# CAN.net
KiCad netlist of a schematic drawn in Altium Designer
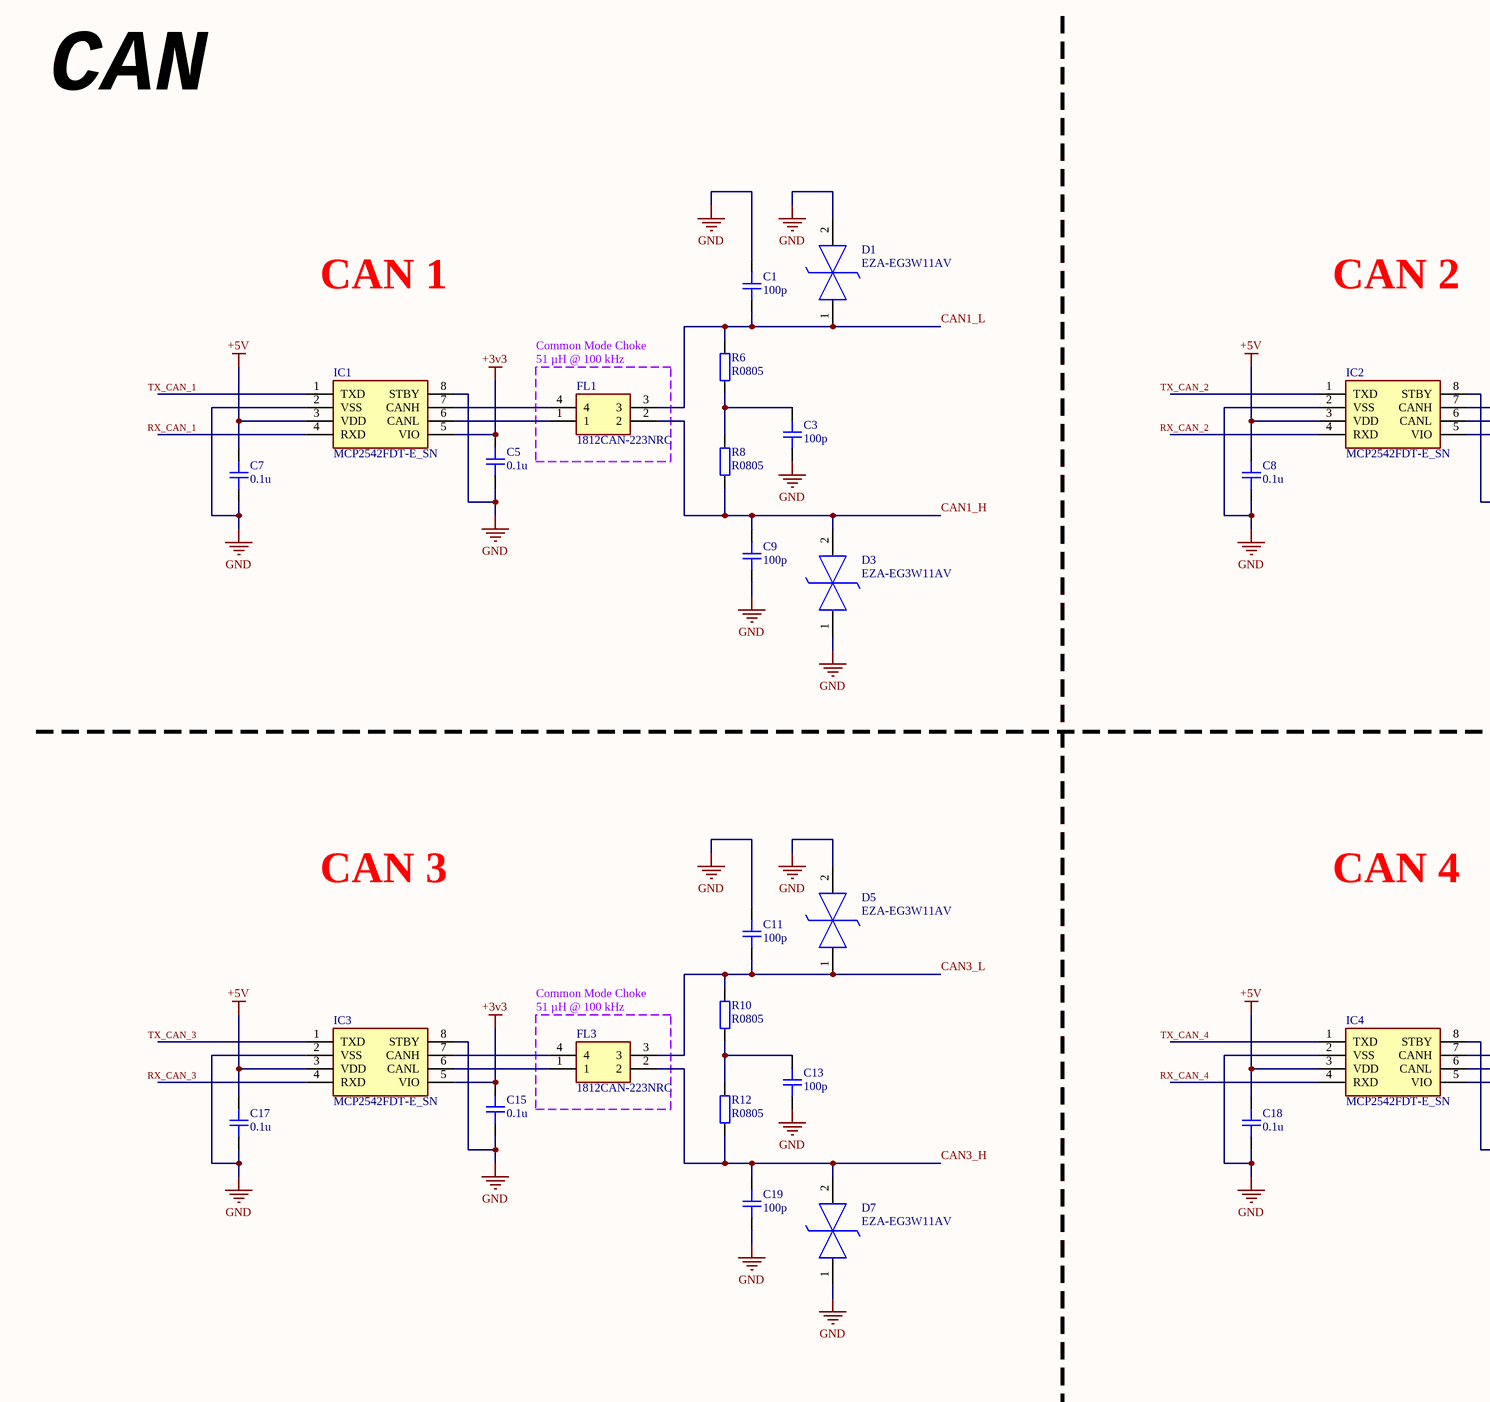
[diagram p0: CAN.SchDoc, left]
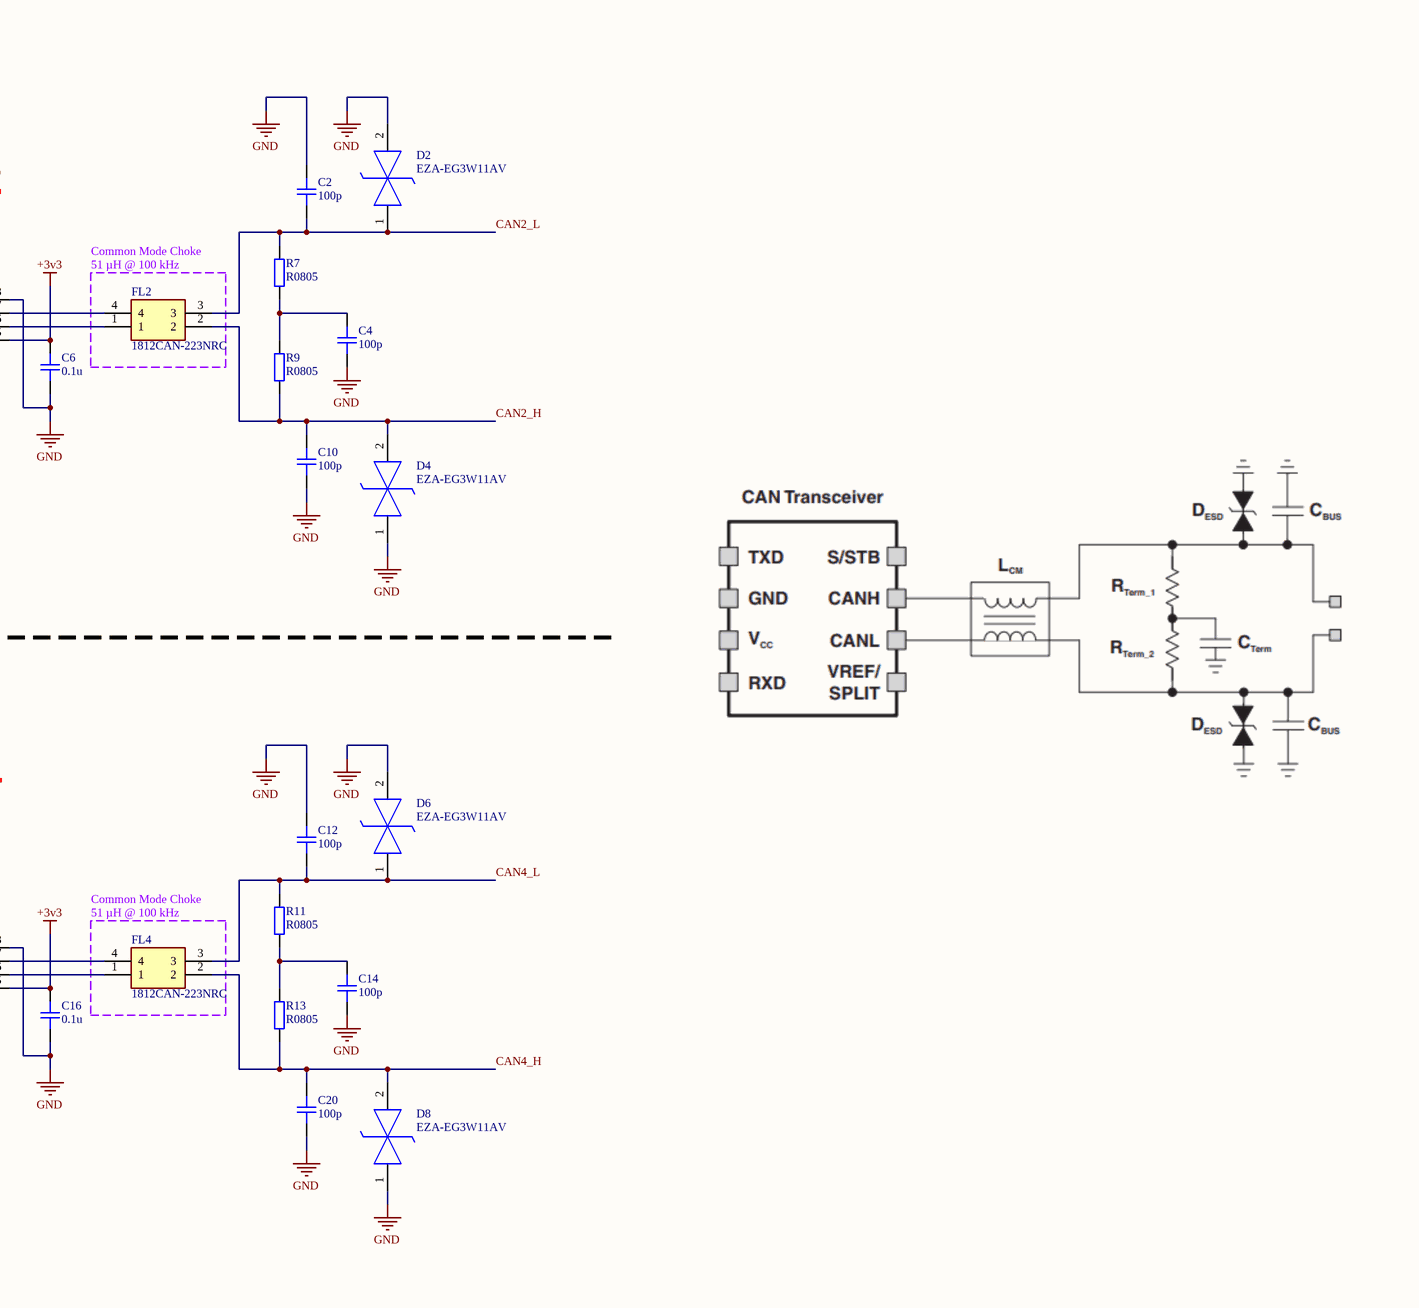
[diagram p1: CAN.SchDoc, right]

(export (version "E")
  (design (tool "Eeschema 10.0.6"))
  (components
    (comp (ref "C1")
      (value "100p")
      (footprint "CAP_0805")
      (description "Capacitor SMD 0805 10V")
      (libsource (lib "Schematic-Lib-PhilsLab") (part "CAP_0805_10V"))
    )
    (comp (ref "C2")
      (value "100p")
      (footprint "CAP_0805")
      (description "Capacitor SMD 0805 10V")
      (libsource (lib "Schematic-Lib-PhilsLab") (part "CAP_0805_10V"))
    )
    (comp (ref "C3")
      (value "100p")
      (footprint "CAP_0805")
      (description "Capacitor SMD 0805 10V")
      (libsource (lib "Schematic-Lib-PhilsLab") (part "CAP_0805_10V"))
    )
    (comp (ref "C4")
      (value "100p")
      (footprint "CAP_0805")
      (description "Capacitor SMD 0805 10V")
      (libsource (lib "Schematic-Lib-PhilsLab") (part "CAP_0805_10V"))
    )
    (comp (ref "C5")
      (value "0.1u")
      (footprint "CAP_0805")
      (description "Capacitor SMD 0805 10V")
      (libsource (lib "Schematic-Lib-PhilsLab") (part "CAP_0805_10V"))
    )
    (comp (ref "C6")
      (value "0.1u")
      (footprint "CAP_0805")
      (description "Capacitor SMD 0805 10V")
      (libsource (lib "Schematic-Lib-PhilsLab") (part "CAP_0805_10V"))
    )
    (comp (ref "C7")
      (value "0.1u")
      (footprint "CAP_0805")
      (description "Capacitor SMD 0805 10V")
      (libsource (lib "Schematic-Lib-PhilsLab") (part "CAP_0805_10V"))
    )
    (comp (ref "C8")
      (value "0.1u")
      (footprint "CAP_0805")
      (description "Capacitor SMD 0805 10V")
      (libsource (lib "Schematic-Lib-PhilsLab") (part "CAP_0805_10V"))
    )
    (comp (ref "C9")
      (value "100p")
      (footprint "CAP_0805")
      (description "Capacitor SMD 0805 10V")
      (libsource (lib "Schematic-Lib-PhilsLab") (part "CAP_0805_10V"))
    )
    (comp (ref "C10")
      (value "100p")
      (footprint "CAP_0805")
      (description "Capacitor SMD 0805 10V")
      (libsource (lib "Schematic-Lib-PhilsLab") (part "CAP_0805_10V"))
    )
    (comp (ref "C11")
      (value "100p")
      (footprint "CAP_0805")
      (description "Capacitor SMD 0805 10V")
      (libsource (lib "Schematic-Lib-PhilsLab") (part "CAP_0805_10V"))
    )
    (comp (ref "C12")
      (value "100p")
      (footprint "CAP_0805")
      (description "Capacitor SMD 0805 10V")
      (libsource (lib "Schematic-Lib-PhilsLab") (part "CAP_0805_10V"))
    )
    (comp (ref "C13")
      (value "100p")
      (footprint "CAP_0805")
      (description "Capacitor SMD 0805 10V")
      (libsource (lib "Schematic-Lib-PhilsLab") (part "CAP_0805_10V"))
    )
    (comp (ref "C14")
      (value "100p")
      (footprint "CAP_0805")
      (description "Capacitor SMD 0805 10V")
      (libsource (lib "Schematic-Lib-PhilsLab") (part "CAP_0805_10V"))
    )
    (comp (ref "C15")
      (value "0.1u")
      (footprint "CAP_0805")
      (description "Capacitor SMD 0805 10V")
      (libsource (lib "Schematic-Lib-PhilsLab") (part "CAP_0805_10V"))
    )
    (comp (ref "C16")
      (value "0.1u")
      (footprint "CAP_0805")
      (description "Capacitor SMD 0805 10V")
      (libsource (lib "Schematic-Lib-PhilsLab") (part "CAP_0805_10V"))
    )
    (comp (ref "C17")
      (value "0.1u")
      (footprint "CAP_0805")
      (description "Capacitor SMD 0805 10V")
      (libsource (lib "Schematic-Lib-PhilsLab") (part "CAP_0805_10V"))
    )
    (comp (ref "C18")
      (value "0.1u")
      (footprint "CAP_0805")
      (description "Capacitor SMD 0805 10V")
      (libsource (lib "Schematic-Lib-PhilsLab") (part "CAP_0805_10V"))
    )
    (comp (ref "C19")
      (value "100p")
      (footprint "CAP_0805")
      (description "Capacitor SMD 0805 10V")
      (libsource (lib "Schematic-Lib-PhilsLab") (part "CAP_0805_10V"))
    )
    (comp (ref "C20")
      (value "100p")
      (footprint "CAP_0805")
      (description "Capacitor SMD 0805 10V")
      (libsource (lib "Schematic-Lib-PhilsLab") (part "CAP_0805_10V"))
    )
    (comp (ref "D1")
      (value "EZA-EG3W11AV")
      (footprint "EZAEG3W11AV")
      (description "Diode ESD (Bi-directional)")
      (fields (field (name "MOUSER PART NUMBER") "667-EZA-EG3W11AV"))
      (libsource (lib "Pedro_Integrated_Library") (part "EZA-EG3W11AV"))
    )
    (comp (ref "D2")
      (value "EZA-EG3W11AV")
      (footprint "EZAEG3W11AV")
      (description "Diode ESD (Bi-directional)")
      (fields (field (name "MOUSER PART NUMBER") "667-EZA-EG3W11AV"))
      (libsource (lib "Pedro_Integrated_Library") (part "EZA-EG3W11AV"))
    )
    (comp (ref "D3")
      (value "EZA-EG3W11AV")
      (footprint "EZAEG3W11AV")
      (description "Diode ESD (Bi-directional)")
      (fields (field (name "MOUSER PART NUMBER") "667-EZA-EG3W11AV"))
      (libsource (lib "Pedro_Integrated_Library") (part "EZA-EG3W11AV"))
    )
    (comp (ref "D4")
      (value "EZA-EG3W11AV")
      (footprint "EZAEG3W11AV")
      (description "Diode ESD (Bi-directional)")
      (fields (field (name "MOUSER PART NUMBER") "667-EZA-EG3W11AV"))
      (libsource (lib "Pedro_Integrated_Library") (part "EZA-EG3W11AV"))
    )
    (comp (ref "D5")
      (value "EZA-EG3W11AV")
      (footprint "EZAEG3W11AV")
      (description "Diode ESD (Bi-directional)")
      (fields (field (name "MOUSER PART NUMBER") "667-EZA-EG3W11AV"))
      (libsource (lib "Pedro_Integrated_Library") (part "EZA-EG3W11AV"))
    )
    (comp (ref "D6")
      (value "EZA-EG3W11AV")
      (footprint "EZAEG3W11AV")
      (description "Diode ESD (Bi-directional)")
      (fields (field (name "MOUSER PART NUMBER") "667-EZA-EG3W11AV"))
      (libsource (lib "Pedro_Integrated_Library") (part "EZA-EG3W11AV"))
    )
    (comp (ref "D7")
      (value "EZA-EG3W11AV")
      (footprint "EZAEG3W11AV")
      (description "Diode ESD (Bi-directional)")
      (fields (field (name "MOUSER PART NUMBER") "667-EZA-EG3W11AV"))
      (libsource (lib "Pedro_Integrated_Library") (part "EZA-EG3W11AV"))
    )
    (comp (ref "D8")
      (value "EZA-EG3W11AV")
      (footprint "EZAEG3W11AV")
      (description "Diode ESD (Bi-directional)")
      (fields (field (name "MOUSER PART NUMBER") "667-EZA-EG3W11AV"))
      (libsource (lib "Pedro_Integrated_Library") (part "EZA-EG3W11AV"))
    )
    (comp (ref "FL1")
      (value "1812CAN-223NRC")
      (footprint "1812CAN223NRC")
      (description "Filter")
      (fields (field (name "MOUSER PART NUMBER") "994-1812CAN-223NRC"))
      (libsource (lib "Pedro_Integrated_Library") (part "1812CAN-223NRC"))
    )
    (comp (ref "FL2")
      (value "1812CAN-223NRC")
      (footprint "1812CAN223NRC")
      (description "Filter")
      (fields (field (name "MOUSER PART NUMBER") "994-1812CAN-223NRC"))
      (libsource (lib "Pedro_Integrated_Library") (part "1812CAN-223NRC"))
    )
    (comp (ref "FL3")
      (value "1812CAN-223NRC")
      (footprint "1812CAN223NRC")
      (description "Filter")
      (fields (field (name "MOUSER PART NUMBER") "994-1812CAN-223NRC"))
      (libsource (lib "Pedro_Integrated_Library") (part "1812CAN-223NRC"))
    )
    (comp (ref "FL4")
      (value "1812CAN-223NRC")
      (footprint "1812CAN223NRC")
      (description "Filter")
      (fields (field (name "MOUSER PART NUMBER") "994-1812CAN-223NRC"))
      (libsource (lib "Pedro_Integrated_Library") (part "1812CAN-223NRC"))
    )
    (comp (ref "IC1")
      (value "MCP2542FDT-E_SN")
      (footprint "SOIC127P600X175-8N")
      (description "Integrated Circuit")
      (fields
        (field (name "MANUFACTURER_PART_NUMBER") "MCP2542FDT-E/SN")
        (field (name "MOUSER PART NUMBER") "579-MCP2542FDT-E/SN")
      )
      (libsource (lib "*") (part "MCP2542FDT-E_SN"))
    )
    (comp (ref "IC2")
      (value "MCP2542FDT-E_SN")
      (footprint "SOIC127P600X175-8N")
      (description "Integrated Circuit")
      (fields
        (field (name "MANUFACTURER_PART_NUMBER") "MCP2542FDT-E/SN")
        (field (name "MOUSER PART NUMBER") "579-MCP2542FDT-E/SN")
      )
      (libsource (lib "*") (part "MCP2542FDT-E_SN"))
    )
    (comp (ref "IC3")
      (value "MCP2542FDT-E_SN")
      (footprint "SOIC127P600X175-8N")
      (description "Integrated Circuit")
      (fields
        (field (name "MANUFACTURER_PART_NUMBER") "MCP2542FDT-E/SN")
        (field (name "MOUSER PART NUMBER") "579-MCP2542FDT-E/SN")
      )
      (libsource (lib "*") (part "MCP2542FDT-E_SN"))
    )
    (comp (ref "IC4")
      (value "MCP2542FDT-E_SN")
      (footprint "SOIC127P600X175-8N")
      (description "Integrated Circuit")
      (fields
        (field (name "MANUFACTURER_PART_NUMBER") "MCP2542FDT-E/SN")
        (field (name "MOUSER PART NUMBER") "579-MCP2542FDT-E/SN")
      )
      (libsource (lib "*") (part "MCP2542FDT-E_SN"))
    )
    (comp (ref "R6")
      (value "R0805")
      (footprint "RES_0805")
      (description "Resistor SMD 0805")
      (libsource (lib "Schematic-Lib-PhilsLab") (part "RES_0805"))
    )
    (comp (ref "R7")
      (value "R0805")
      (footprint "RES_0805")
      (description "Resistor SMD 0805")
      (libsource (lib "Schematic-Lib-PhilsLab") (part "RES_0805"))
    )
    (comp (ref "R8")
      (value "R0805")
      (footprint "RES_0805")
      (description "Resistor SMD 0805")
      (libsource (lib "Schematic-Lib-PhilsLab") (part "RES_0805"))
    )
    (comp (ref "R9")
      (value "R0805")
      (footprint "RES_0805")
      (description "Resistor SMD 0805")
      (libsource (lib "Schematic-Lib-PhilsLab") (part "RES_0805"))
    )
    (comp (ref "R10")
      (value "R0805")
      (footprint "RES_0805")
      (description "Resistor SMD 0805")
      (libsource (lib "Schematic-Lib-PhilsLab") (part "RES_0805"))
    )
    (comp (ref "R11")
      (value "R0805")
      (footprint "RES_0805")
      (description "Resistor SMD 0805")
      (libsource (lib "Schematic-Lib-PhilsLab") (part "RES_0805"))
    )
    (comp (ref "R12")
      (value "R0805")
      (footprint "RES_0805")
      (description "Resistor SMD 0805")
      (libsource (lib "Schematic-Lib-PhilsLab") (part "RES_0805"))
    )
    (comp (ref "R13")
      (value "R0805")
      (footprint "RES_0805")
      (description "Resistor SMD 0805")
      (libsource (lib "Schematic-Lib-PhilsLab") (part "RES_0805"))
    )
  )
  (nets
    (net (code "1") (name "+3v3") (class "Default")
      (node (ref "C15") (pin "2") (pinfunction "2_2") (pintype "passive"))
      (node (ref "C16") (pin "2") (pinfunction "2_2") (pintype "passive"))
      (node (ref "C5") (pin "2") (pinfunction "2_2") (pintype "passive"))
      (node (ref "C6") (pin "2") (pinfunction "2_2") (pintype "passive"))
      (node (ref "IC1") (pin "5") (pinfunction "VIO_5") (pintype "passive"))
      (node (ref "IC2") (pin "5") (pinfunction "VIO_5") (pintype "passive"))
      (node (ref "IC3") (pin "5") (pinfunction "VIO_5") (pintype "passive"))
      (node (ref "IC4") (pin "5") (pinfunction "VIO_5") (pintype "passive"))
    )
    (net (code "2") (name "+5V") (class "Default")
      (node (ref "C17") (pin "2") (pinfunction "2_2") (pintype "passive"))
      (node (ref "C18") (pin "2") (pinfunction "2_2") (pintype "passive"))
      (node (ref "C7") (pin "2") (pinfunction "2_2") (pintype "passive"))
      (node (ref "C8") (pin "2") (pinfunction "2_2") (pintype "passive"))
      (node (ref "IC1") (pin "3") (pinfunction "VDD_3") (pintype "passive"))
      (node (ref "IC2") (pin "3") (pinfunction "VDD_3") (pintype "passive"))
      (node (ref "IC3") (pin "3") (pinfunction "VDD_3") (pintype "passive"))
      (node (ref "IC4") (pin "3") (pinfunction "VDD_3") (pintype "passive"))
    )
    (net (code "3") (name "/CAN1_H") (class "Default")
      (node (ref "C9") (pin "1") (pinfunction "1_1") (pintype "passive"))
      (node (ref "D3") (pin "2") (pinfunction "K2_2") (pintype "passive"))
      (node (ref "FL1") (pin "2") (pinfunction "2_2") (pintype "passive"))
      (node (ref "R8") (pin "1") (pinfunction "1_1") (pintype "passive"))
    )
    (net (code "4") (name "/CAN1_L") (class "Default")
      (node (ref "C1") (pin "2") (pinfunction "2_2") (pintype "passive"))
      (node (ref "D1") (pin "1") (pinfunction "K1_1") (pintype "passive"))
      (node (ref "FL1") (pin "3") (pinfunction "3_3") (pintype "passive"))
      (node (ref "R6") (pin "2") (pinfunction "2_2") (pintype "passive"))
    )
    (net (code "5") (name "/CAN2_H") (class "Default")
      (node (ref "C10") (pin "1") (pinfunction "1_1") (pintype "passive"))
      (node (ref "D4") (pin "2") (pinfunction "K2_2") (pintype "passive"))
      (node (ref "FL2") (pin "2") (pinfunction "2_2") (pintype "passive"))
      (node (ref "R9") (pin "1") (pinfunction "1_1") (pintype "passive"))
    )
    (net (code "6") (name "/CAN2_L") (class "Default")
      (node (ref "C2") (pin "2") (pinfunction "2_2") (pintype "passive"))
      (node (ref "D2") (pin "1") (pinfunction "K1_1") (pintype "passive"))
      (node (ref "FL2") (pin "3") (pinfunction "3_3") (pintype "passive"))
      (node (ref "R7") (pin "2") (pinfunction "2_2") (pintype "passive"))
    )
    (net (code "7") (name "/CAN3_H") (class "Default")
      (node (ref "C19") (pin "1") (pinfunction "1_1") (pintype "passive"))
      (node (ref "D7") (pin "2") (pinfunction "K2_2") (pintype "passive"))
      (node (ref "FL3") (pin "2") (pinfunction "2_2") (pintype "passive"))
      (node (ref "R12") (pin "1") (pinfunction "1_1") (pintype "passive"))
    )
    (net (code "8") (name "/CAN3_L") (class "Default")
      (node (ref "C11") (pin "2") (pinfunction "2_2") (pintype "passive"))
      (node (ref "D5") (pin "1") (pinfunction "K1_1") (pintype "passive"))
      (node (ref "FL3") (pin "3") (pinfunction "3_3") (pintype "passive"))
      (node (ref "R10") (pin "2") (pinfunction "2_2") (pintype "passive"))
    )
    (net (code "9") (name "/CAN4_H") (class "Default")
      (node (ref "C20") (pin "1") (pinfunction "1_1") (pintype "passive"))
      (node (ref "D8") (pin "2") (pinfunction "K2_2") (pintype "passive"))
      (node (ref "FL4") (pin "2") (pinfunction "2_2") (pintype "passive"))
      (node (ref "R13") (pin "1") (pinfunction "1_1") (pintype "passive"))
    )
    (net (code "10") (name "/CAN4_L") (class "Default")
      (node (ref "C12") (pin "2") (pinfunction "2_2") (pintype "passive"))
      (node (ref "D6") (pin "1") (pinfunction "K1_1") (pintype "passive"))
      (node (ref "FL4") (pin "3") (pinfunction "3_3") (pintype "passive"))
      (node (ref "R11") (pin "2") (pinfunction "2_2") (pintype "passive"))
    )
    (net (code "11") (name "/RX_CAN_1") (class "Default")
      (node (ref "IC1") (pin "4") (pinfunction "RXD_4") (pintype "passive"))
    )
    (net (code "12") (name "/RX_CAN_2") (class "Default")
      (node (ref "IC2") (pin "4") (pinfunction "RXD_4") (pintype "passive"))
    )
    (net (code "13") (name "/RX_CAN_3") (class "Default")
      (node (ref "IC3") (pin "4") (pinfunction "RXD_4") (pintype "passive"))
    )
    (net (code "14") (name "/RX_CAN_4") (class "Default")
      (node (ref "IC4") (pin "4") (pinfunction "RXD_4") (pintype "passive"))
    )
    (net (code "15") (name "/TX_CAN_1") (class "Default")
      (node (ref "IC1") (pin "1") (pinfunction "TXD_1") (pintype "passive"))
    )
    (net (code "16") (name "/TX_CAN_2") (class "Default")
      (node (ref "IC2") (pin "1") (pinfunction "TXD_1") (pintype "passive"))
    )
    (net (code "17") (name "/TX_CAN_3") (class "Default")
      (node (ref "IC3") (pin "1") (pinfunction "TXD_1") (pintype "passive"))
    )
    (net (code "18") (name "/TX_CAN_4") (class "Default")
      (node (ref "IC4") (pin "1") (pinfunction "TXD_1") (pintype "passive"))
    )
    (net (code "19") (name "GND") (class "Default")
      (node (ref "C1") (pin "1") (pinfunction "1_1") (pintype "passive"))
      (node (ref "C10") (pin "2") (pinfunction "2_2") (pintype "passive"))
      (node (ref "C11") (pin "1") (pinfunction "1_1") (pintype "passive"))
      (node (ref "C12") (pin "1") (pinfunction "1_1") (pintype "passive"))
      (node (ref "C13") (pin "2") (pinfunction "2_2") (pintype "passive"))
      (node (ref "C14") (pin "2") (pinfunction "2_2") (pintype "passive"))
      (node (ref "C15") (pin "1") (pinfunction "1_1") (pintype "passive"))
      (node (ref "C16") (pin "1") (pinfunction "1_1") (pintype "passive"))
      (node (ref "C17") (pin "1") (pinfunction "1_1") (pintype "passive"))
      (node (ref "C18") (pin "1") (pinfunction "1_1") (pintype "passive"))
      (node (ref "C19") (pin "2") (pinfunction "2_2") (pintype "passive"))
      (node (ref "C2") (pin "1") (pinfunction "1_1") (pintype "passive"))
      (node (ref "C20") (pin "2") (pinfunction "2_2") (pintype "passive"))
      (node (ref "C3") (pin "2") (pinfunction "2_2") (pintype "passive"))
      (node (ref "C4") (pin "2") (pinfunction "2_2") (pintype "passive"))
      (node (ref "C5") (pin "1") (pinfunction "1_1") (pintype "passive"))
      (node (ref "C6") (pin "1") (pinfunction "1_1") (pintype "passive"))
      (node (ref "C7") (pin "1") (pinfunction "1_1") (pintype "passive"))
      (node (ref "C8") (pin "1") (pinfunction "1_1") (pintype "passive"))
      (node (ref "C9") (pin "2") (pinfunction "2_2") (pintype "passive"))
      (node (ref "D1") (pin "2") (pinfunction "K2_2") (pintype "passive"))
      (node (ref "D2") (pin "2") (pinfunction "K2_2") (pintype "passive"))
      (node (ref "D3") (pin "1") (pinfunction "K1_1") (pintype "passive"))
      (node (ref "D4") (pin "1") (pinfunction "K1_1") (pintype "passive"))
      (node (ref "D5") (pin "2") (pinfunction "K2_2") (pintype "passive"))
      (node (ref "D6") (pin "2") (pinfunction "K2_2") (pintype "passive"))
      (node (ref "D7") (pin "1") (pinfunction "K1_1") (pintype "passive"))
      (node (ref "D8") (pin "1") (pinfunction "K1_1") (pintype "passive"))
      (node (ref "IC1") (pin "2") (pinfunction "VSS_2") (pintype "passive"))
      (node (ref "IC1") (pin "8") (pinfunction "STBY_8") (pintype "passive"))
      (node (ref "IC2") (pin "2") (pinfunction "VSS_2") (pintype "passive"))
      (node (ref "IC2") (pin "8") (pinfunction "STBY_8") (pintype "passive"))
      (node (ref "IC3") (pin "2") (pinfunction "VSS_2") (pintype "passive"))
      (node (ref "IC3") (pin "8") (pinfunction "STBY_8") (pintype "passive"))
      (node (ref "IC4") (pin "2") (pinfunction "VSS_2") (pintype "passive"))
      (node (ref "IC4") (pin "8") (pinfunction "STBY_8") (pintype "passive"))
    )
    (net (code "20") (name "Net-(C3-Pad1)") (class "Default")
      (node (ref "C3") (pin "1") (pinfunction "1_1") (pintype "passive"))
      (node (ref "R6") (pin "1") (pinfunction "1_1") (pintype "passive"))
      (node (ref "R8") (pin "2") (pinfunction "2_2") (pintype "passive"))
    )
    (net (code "21") (name "Net-(C4-Pad1)") (class "Default")
      (node (ref "C4") (pin "1") (pinfunction "1_1") (pintype "passive"))
      (node (ref "R7") (pin "1") (pinfunction "1_1") (pintype "passive"))
      (node (ref "R9") (pin "2") (pinfunction "2_2") (pintype "passive"))
    )
    (net (code "22") (name "Net-(C13-Pad1)") (class "Default")
      (node (ref "C13") (pin "1") (pinfunction "1_1") (pintype "passive"))
      (node (ref "R10") (pin "1") (pinfunction "1_1") (pintype "passive"))
      (node (ref "R12") (pin "2") (pinfunction "2_2") (pintype "passive"))
    )
    (net (code "23") (name "Net-(C14-Pad1)") (class "Default")
      (node (ref "C14") (pin "1") (pinfunction "1_1") (pintype "passive"))
      (node (ref "R11") (pin "1") (pinfunction "1_1") (pintype "passive"))
      (node (ref "R13") (pin "2") (pinfunction "2_2") (pintype "passive"))
    )
    (net (code "24") (name "Net-(IC1-CANH)") (class "Default")
      (node (ref "FL1") (pin "4") (pinfunction "4_4") (pintype "passive"))
      (node (ref "IC1") (pin "7") (pinfunction "CANH_7") (pintype "passive"))
    )
    (net (code "25") (name "Net-(IC1-CANL)") (class "Default")
      (node (ref "FL1") (pin "1") (pinfunction "1_1") (pintype "passive"))
      (node (ref "IC1") (pin "6") (pinfunction "CANL_6") (pintype "passive"))
    )
    (net (code "26") (name "Net-(IC2-CANH)") (class "Default")
      (node (ref "FL2") (pin "4") (pinfunction "4_4") (pintype "passive"))
      (node (ref "IC2") (pin "7") (pinfunction "CANH_7") (pintype "passive"))
    )
    (net (code "27") (name "Net-(IC2-CANL)") (class "Default")
      (node (ref "FL2") (pin "1") (pinfunction "1_1") (pintype "passive"))
      (node (ref "IC2") (pin "6") (pinfunction "CANL_6") (pintype "passive"))
    )
    (net (code "28") (name "Net-(IC3-CANH)") (class "Default")
      (node (ref "FL3") (pin "4") (pinfunction "4_4") (pintype "passive"))
      (node (ref "IC3") (pin "7") (pinfunction "CANH_7") (pintype "passive"))
    )
    (net (code "29") (name "Net-(IC3-CANL)") (class "Default")
      (node (ref "FL3") (pin "1") (pinfunction "1_1") (pintype "passive"))
      (node (ref "IC3") (pin "6") (pinfunction "CANL_6") (pintype "passive"))
    )
    (net (code "30") (name "Net-(IC4-CANH)") (class "Default")
      (node (ref "FL4") (pin "4") (pinfunction "4_4") (pintype "passive"))
      (node (ref "IC4") (pin "7") (pinfunction "CANH_7") (pintype "passive"))
    )
    (net (code "31") (name "Net-(IC4-CANL)") (class "Default")
      (node (ref "FL4") (pin "1") (pinfunction "1_1") (pintype "passive"))
      (node (ref "IC4") (pin "6") (pinfunction "CANL_6") (pintype "passive"))
    )
  )
)
